# microzed_sd_v0_5_r1_1.net
KiCad netlist of a schematic drawn in EAGLE
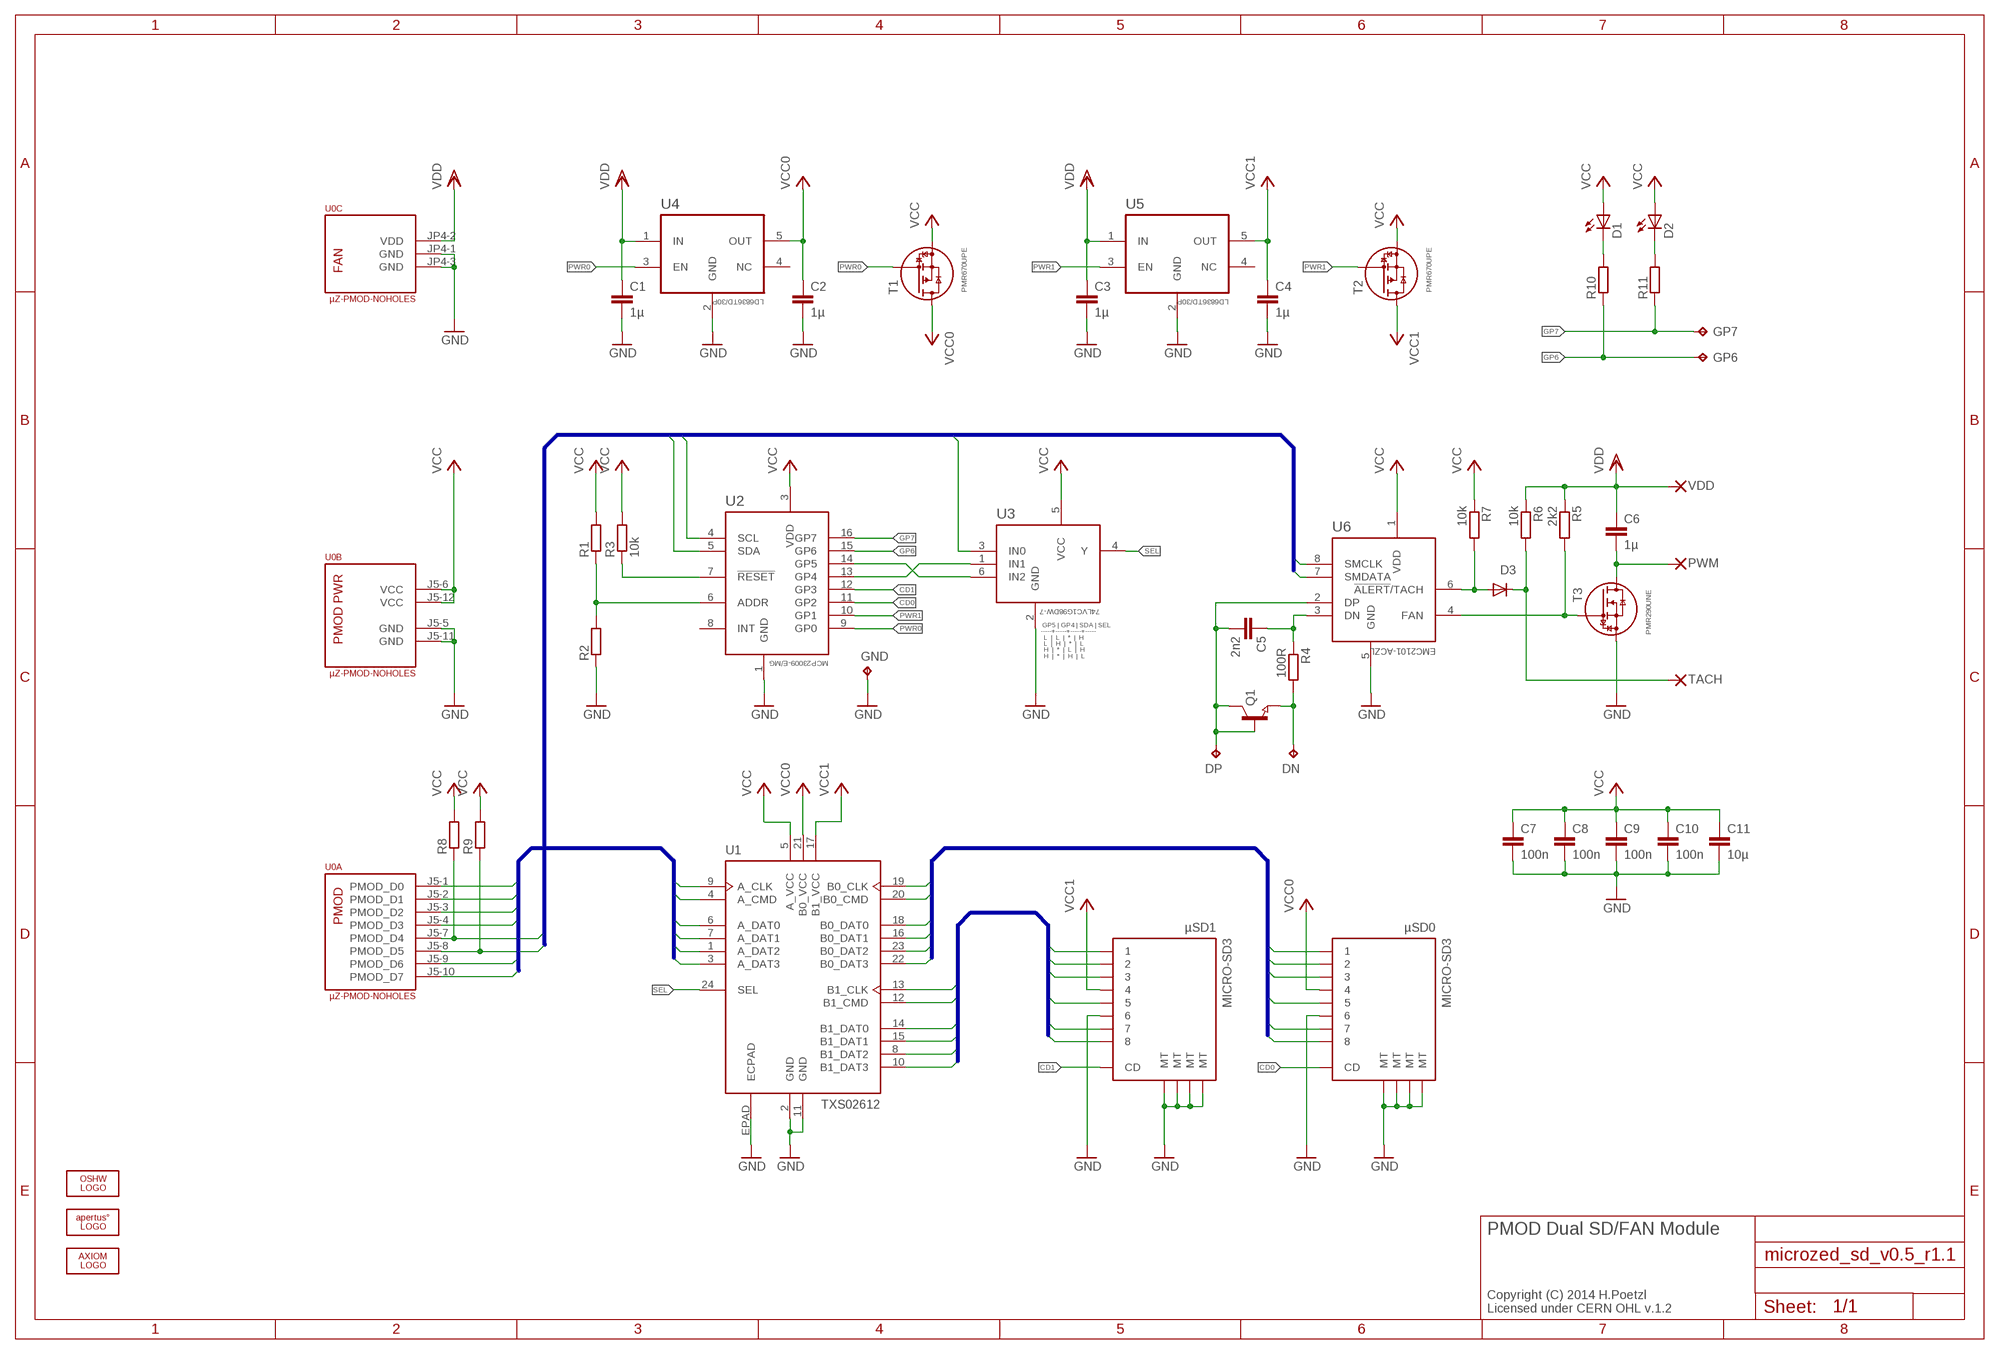
[diagram p0: schematic, sheet 1]

(export (version "E")
  (design (tool "Eeschema 10.0.6"))
  (components
    (comp (ref "C1")
      (value "1µ")
      (footprint "eagle-import:C0402K")
      (libsource (lib "eagle-import") (part "C-EUC0402K"))
    )
    (comp (ref "C2")
      (value "1µ")
      (footprint "eagle-import:C0402K")
      (libsource (lib "eagle-import") (part "C-EUC0402K"))
    )
    (comp (ref "C3")
      (value "1µ")
      (footprint "eagle-import:C0402K")
      (libsource (lib "eagle-import") (part "C-EUC0402K"))
    )
    (comp (ref "C4")
      (value "1µ")
      (footprint "eagle-import:C0402K")
      (libsource (lib "eagle-import") (part "C-EUC0402K"))
    )
    (comp (ref "C5")
      (value "2n2")
      (footprint "eagle-import:C0402K")
      (libsource (lib "eagle-import") (part "C-EUC0402K"))
    )
    (comp (ref "C6")
      (value "1µ")
      (footprint "eagle-import:C0402K")
      (libsource (lib "eagle-import") (part "C-EUC0402K"))
    )
    (comp (ref "C7")
      (value "100n")
      (footprint "eagle-import:C0402K")
      (libsource (lib "eagle-import") (part "C-EUC0402K"))
    )
    (comp (ref "C8")
      (value "100n")
      (footprint "eagle-import:C0402K")
      (libsource (lib "eagle-import") (part "C-EUC0402K"))
    )
    (comp (ref "C9")
      (value "100n")
      (footprint "eagle-import:C0402K")
      (libsource (lib "eagle-import") (part "C-EUC0402K"))
    )
    (comp (ref "C10")
      (value "100n")
      (footprint "eagle-import:C0402K")
      (libsource (lib "eagle-import") (part "C-EUC0402K"))
    )
    (comp (ref "C11")
      (value "10µ")
      (footprint "eagle-import:C0603K")
      (libsource (lib "eagle-import") (part "C-EUC0603K"))
    )
    (comp (ref "D1")
      (value "LEDCHIPLED_0603")
      (footprint "eagle-import:CHIPLED_0603")
      (libsource (lib "eagle-import") (part "LEDCHIPLED_0603"))
    )
    (comp (ref "D2")
      (value "LEDCHIPLED_0603")
      (footprint "eagle-import:CHIPLED_0603")
      (libsource (lib "eagle-import") (part "LEDCHIPLED_0603"))
    )
    (comp (ref "D3")
      (value "DIODE-MICROMELF-W")
      (footprint "eagle-import:MICROMELF-W")
      (libsource (lib "eagle-import") (part "DIODE-MICROMELF-W"))
    )
    (comp (ref "DN")
      (value "TPTP20R")
      (footprint "eagle-import:TP20R")
      (libsource (lib "eagle-import") (part "TPTP20R"))
    )
    (comp (ref "DP")
      (value "TPTP20R")
      (footprint "eagle-import:TP20R")
      (libsource (lib "eagle-import") (part "TPTP20R"))
    )
    (comp (ref "GND")
      (value "TPTP20R")
      (footprint "eagle-import:TP20R")
      (libsource (lib "eagle-import") (part "TPTP20R"))
    )
    (comp (ref "GP6")
      (value "TPTP20R")
      (footprint "eagle-import:TP20R")
      (libsource (lib "eagle-import") (part "TPTP20R"))
    )
    (comp (ref "GP7")
      (value "TPTP20R")
      (footprint "eagle-import:TP20R")
      (libsource (lib "eagle-import") (part "TPTP20R"))
    )
    (comp (ref "LOGO1")
      (value "OSHW_LOGO_FILLX0100-NT")
      (footprint "eagle-import:OSHW_FILLX100_NOTEXT")
      (libsource (lib "eagle-import") (part "OSHW_LOGO_FILLX0100-NT"))
    )
    (comp (ref "PWM")
      (value "WIREPAD1,85/1,0_SQ")
      (footprint "eagle-import:1,85_1,0_SQ")
      (libsource (lib "eagle-import") (part "WIREPAD1,85/1,0_SQ"))
    )
    (comp (ref "Q1")
      (value "NPN-TRANSISTOR_SOT23")
      (footprint "eagle-import:SOT23")
      (libsource (lib "eagle-import") (part "NPN-TRANSISTOR_SOT23"))
    )
    (comp (ref "R1")
      (value "R-EU_R0402")
      (footprint "eagle-import:R0402")
      (libsource (lib "eagle-import") (part "R-EU_R0402"))
    )
    (comp (ref "R2")
      (value "R-EU_R0402")
      (footprint "eagle-import:R0402")
      (libsource (lib "eagle-import") (part "R-EU_R0402"))
    )
    (comp (ref "R3")
      (value "10k")
      (footprint "eagle-import:R0402")
      (libsource (lib "eagle-import") (part "R-EU_R0402"))
    )
    (comp (ref "R4")
      (value "100R")
      (footprint "eagle-import:R0402")
      (libsource (lib "eagle-import") (part "R-EU_R0402"))
    )
    (comp (ref "R5")
      (value "2k2")
      (footprint "eagle-import:R0402")
      (libsource (lib "eagle-import") (part "R-EU_R0402"))
    )
    (comp (ref "R6")
      (value "10k")
      (footprint "eagle-import:R0402")
      (libsource (lib "eagle-import") (part "R-EU_R0402"))
    )
    (comp (ref "R7")
      (value "10k")
      (footprint "eagle-import:R0402")
      (libsource (lib "eagle-import") (part "R-EU_R0402"))
    )
    (comp (ref "R8")
      (value "R-EU_R0402")
      (footprint "eagle-import:R0402")
      (libsource (lib "eagle-import") (part "R-EU_R0402"))
    )
    (comp (ref "R9")
      (value "R-EU_R0402")
      (footprint "eagle-import:R0402")
      (libsource (lib "eagle-import") (part "R-EU_R0402"))
    )
    (comp (ref "R10")
      (value "R-EU_R0402")
      (footprint "eagle-import:R0402")
      (libsource (lib "eagle-import") (part "R-EU_R0402"))
    )
    (comp (ref "R11")
      (value "R-EU_R0402")
      (footprint "eagle-import:R0402")
      (libsource (lib "eagle-import") (part "R-EU_R0402"))
    )
    (comp (ref "T1")
      (value "PMR670UPE")
      (footprint "eagle-import:SOT416")
      (libsource (lib "eagle-import") (part "PMR670UPE"))
    )
    (comp (ref "T2")
      (value "PMR670UPE")
      (footprint "eagle-import:SOT416")
      (libsource (lib "eagle-import") (part "PMR670UPE"))
    )
    (comp (ref "T3")
      (value "PMR290UNE")
      (footprint "eagle-import:SOT416")
      (libsource (lib "eagle-import") (part "PMR290UNE"))
    )
    (comp (ref "TACH")
      (value "WIREPAD1,85/1,0")
      (footprint "eagle-import:1,85_1,0")
      (libsource (lib "eagle-import") (part "WIREPAD1,85/1,0"))
    )
    (comp (ref "U$1")
      (value "APERTUS_LOGO334X100")
      (footprint "eagle-import:APERTUS_LOGO_334X100")
      (libsource (lib "eagle-import") (part "APERTUS_LOGO334X100"))
    )
    (comp (ref "U$13")
      (value "AXIOM_LOGO525X80")
      (footprint "eagle-import:AXIOM_LOGO_525X80")
      (libsource (lib "eagle-import") (part "AXIOM_LOGO525X80"))
    )
    (comp (ref "U0")
      (value "µZ-PMOD-NOHOLES")
      (footprint "eagle-import:µZ-TOP-NOHOLES")
      (libsource (lib "eagle-import") (part "µZ-PMOD-NOHOLES"))
    )
    (comp (ref "U1")
      (value "TXS02612")
      (footprint "eagle-import:S-PWQFN-N24")
      (libsource (lib "eagle-import") (part "TXS02612"))
    )
    (comp (ref "U2")
      (value "MCP23009-E/MG")
      (footprint "eagle-import:QFN50P300X300X80-17N")
      (libsource (lib "eagle-import") (part "MCP23009-E/MG"))
    )
    (comp (ref "U3")
      (value "74LVC1G98DW-7")
      (footprint "eagle-import:SOT65P210X110-6N")
      (libsource (lib "eagle-import") (part "74LVC1G98DW-7"))
    )
    (comp (ref "U4")
      (value "LD6836TD/30P")
      (footprint "eagle-import:SOT95P275X110-5N")
      (libsource (lib "eagle-import") (part "LD6836TD/30P"))
    )
    (comp (ref "U5")
      (value "LD6836TD/30P")
      (footprint "eagle-import:SOT95P275X110-5N")
      (libsource (lib "eagle-import") (part "LD6836TD/30P"))
    )
    (comp (ref "U6")
      (value "EMC2101-ACZL")
      (footprint "eagle-import:SOP65P490X110-8N")
      (fields (field (name "MPN") "EMC2101-ACZL-TR "))
      (libsource (lib "eagle-import") (part "EMC2101-ACZL"))
    )
    (comp (ref "VDD")
      (value "WIREPAD1,85/1,0")
      (footprint "eagle-import:1,85_1,0")
      (libsource (lib "eagle-import") (part "WIREPAD1,85/1,0"))
    )
    (comp (ref "µSD0")
      (value "MICRO-SD3")
      (footprint "eagle-import:TF-MICRO-SD_PP3")
      (libsource (lib "eagle-import") (part "MICRO-SD3"))
    )
    (comp (ref "µSD1")
      (value "MICRO-SD3")
      (footprint "eagle-import:TF-MICRO-SD_PP3")
      (libsource (lib "eagle-import") (part "MICRO-SD3"))
    )
  )
  (nets
    (net (code "1") (name "/A_CLK") (class "Default")
      (node (ref "U0") (pin "J5-4") (pinfunction "PMOD_D3_J5-4") (pintype "bidirectional"))
      (node (ref "U1") (pin "9") (pinfunction "A_CLK_9") (pintype "input"))
    )
    (net (code "2") (name "/A_CMD") (class "Default")
      (node (ref "U0") (pin "J5-3") (pinfunction "PMOD_D2_J5-3") (pintype "bidirectional"))
      (node (ref "U1") (pin "4") (pinfunction "A_CMD_4") (pintype "bidirectional"))
    )
    (net (code "3") (name "/A_DAT0") (class "Default")
      (node (ref "U0") (pin "J5-2") (pinfunction "PMOD_D1_J5-2") (pintype "bidirectional"))
      (node (ref "U1") (pin "6") (pinfunction "A_DAT0_6") (pintype "bidirectional"))
    )
    (net (code "4") (name "/A_DAT1") (class "Default")
      (node (ref "U0") (pin "J5-1") (pinfunction "PMOD_D0_J5-1") (pintype "bidirectional"))
      (node (ref "U1") (pin "7") (pinfunction "A_DAT1_7") (pintype "bidirectional"))
    )
    (net (code "5") (name "/A_DAT2") (class "Default")
      (node (ref "U0") (pin "J5-9") (pinfunction "PMOD_D6_J5-9") (pintype "bidirectional"))
      (node (ref "U1") (pin "1") (pinfunction "A_DAT2_1") (pintype "bidirectional"))
    )
    (net (code "6") (name "/A_DAT3") (class "Default")
      (node (ref "U0") (pin "J5-10") (pinfunction "PMOD_D7_J5-10") (pintype "bidirectional"))
      (node (ref "U1") (pin "3") (pinfunction "A_DAT3_3") (pintype "bidirectional"))
    )
    (net (code "7") (name "/B0_CLK") (class "Default")
      (node (ref "U1") (pin "19") (pinfunction "B0_CLK_19") (pintype "output"))
      (node (ref "µSD0") (pin "5") (pinfunction "5_5") (pintype "bidirectional"))
    )
    (net (code "8") (name "/B0_CMD") (class "Default")
      (node (ref "U1") (pin "20") (pinfunction "B0_CMD_20") (pintype "bidirectional"))
      (node (ref "µSD0") (pin "3") (pinfunction "3_3") (pintype "bidirectional"))
    )
    (net (code "9") (name "/B0_DAT0") (class "Default")
      (node (ref "U1") (pin "18") (pinfunction "B0_DAT0_18") (pintype "bidirectional"))
      (node (ref "µSD0") (pin "7") (pinfunction "7_7") (pintype "bidirectional"))
    )
    (net (code "10") (name "/B0_DAT1") (class "Default")
      (node (ref "U1") (pin "16") (pinfunction "B0_DAT1_16") (pintype "bidirectional"))
      (node (ref "µSD0") (pin "8") (pinfunction "8_8") (pintype "bidirectional"))
    )
    (net (code "11") (name "/B0_DAT2") (class "Default")
      (node (ref "U1") (pin "23") (pinfunction "B0_DAT2_23") (pintype "bidirectional"))
      (node (ref "µSD0") (pin "1") (pinfunction "1_1") (pintype "bidirectional"))
    )
    (net (code "12") (name "/B0_DAT3") (class "Default")
      (node (ref "U1") (pin "22") (pinfunction "B0_DAT3_22") (pintype "bidirectional"))
      (node (ref "µSD0") (pin "2") (pinfunction "2_2") (pintype "bidirectional"))
    )
    (net (code "13") (name "/B1_CLK") (class "Default")
      (node (ref "U1") (pin "13") (pinfunction "B1_CLK_13") (pintype "output"))
      (node (ref "µSD1") (pin "5") (pinfunction "5_5") (pintype "bidirectional"))
    )
    (net (code "14") (name "/B1_CMD") (class "Default")
      (node (ref "U1") (pin "12") (pinfunction "B1_CMD_12") (pintype "bidirectional"))
      (node (ref "µSD1") (pin "3") (pinfunction "3_3") (pintype "bidirectional"))
    )
    (net (code "15") (name "/B1_DAT0") (class "Default")
      (node (ref "U1") (pin "14") (pinfunction "B1_DAT0_14") (pintype "bidirectional"))
      (node (ref "µSD1") (pin "7") (pinfunction "7_7") (pintype "bidirectional"))
    )
    (net (code "16") (name "/B1_DAT1") (class "Default")
      (node (ref "U1") (pin "15") (pinfunction "B1_DAT1_15") (pintype "bidirectional"))
      (node (ref "µSD1") (pin "8") (pinfunction "8_8") (pintype "bidirectional"))
    )
    (net (code "17") (name "/B1_DAT2") (class "Default")
      (node (ref "U1") (pin "8") (pinfunction "B1_DAT2_8") (pintype "bidirectional"))
      (node (ref "µSD1") (pin "1") (pinfunction "1_1") (pintype "bidirectional"))
    )
    (net (code "18") (name "/B1_DAT3") (class "Default")
      (node (ref "U1") (pin "10") (pinfunction "B1_DAT3_10") (pintype "bidirectional"))
      (node (ref "µSD1") (pin "2") (pinfunction "2_2") (pintype "bidirectional"))
    )
    (net (code "19") (name "/SCL") (class "Default")
      (node (ref "R8") (pin "1") (pinfunction "1_1") (pintype "passive"))
      (node (ref "U0") (pin "J5-7") (pinfunction "PMOD_D4_J5-7") (pintype "bidirectional"))
      (node (ref "U2") (pin "4") (pinfunction "SCL_4") (pintype "input"))
      (node (ref "U6") (pin "8") (pinfunction "SMCLK_8") (pintype "input"))
    )
    (net (code "20") (name "/SDA") (class "Default")
      (node (ref "R9") (pin "1") (pinfunction "1_1") (pintype "passive"))
      (node (ref "U0") (pin "J5-8") (pinfunction "PMOD_D5_J5-8") (pintype "bidirectional"))
      (node (ref "U2") (pin "5") (pinfunction "SDA_5") (pintype "bidirectional"))
      (node (ref "U3") (pin "3") (pinfunction "IN0_3") (pintype "input"))
      (node (ref "U6") (pin "7") (pinfunction "SMDATA_7") (pintype "bidirectional"))
    )
    (net (code "21") (name "CD0") (class "Default")
      (node (ref "U2") (pin "11") (pinfunction "GP2_11") (pintype "bidirectional"))
      (node (ref "µSD0") (pin "CD") (pinfunction "CD_CD") (pintype "bidirectional"))
    )
    (net (code "22") (name "CD1") (class "Default")
      (node (ref "U2") (pin "12") (pinfunction "GP3_12") (pintype "bidirectional"))
      (node (ref "µSD1") (pin "CD") (pinfunction "CD_CD") (pintype "bidirectional"))
    )
    (net (code "23") (name "GND") (class "Default")
      (node (ref "C1") (pin "2") (pinfunction "2_2") (pintype "passive"))
      (node (ref "C10") (pin "2") (pinfunction "2_2") (pintype "passive"))
      (node (ref "C11") (pin "2") (pinfunction "2_2") (pintype "passive"))
      (node (ref "C2") (pin "2") (pinfunction "2_2") (pintype "passive"))
      (node (ref "C3") (pin "2") (pinfunction "2_2") (pintype "passive"))
      (node (ref "C4") (pin "2") (pinfunction "2_2") (pintype "passive"))
      (node (ref "C7") (pin "2") (pinfunction "2_2") (pintype "passive"))
      (node (ref "C8") (pin "2") (pinfunction "2_2") (pintype "passive"))
      (node (ref "C9") (pin "2") (pinfunction "2_2") (pintype "passive"))
      (node (ref "GND") (pin "TP") (pinfunction "TP_TP") (pintype "input"))
      (node (ref "R2") (pin "1") (pinfunction "1_1") (pintype "passive"))
      (node (ref "T3") (pin "2") (pinfunction "S_2") (pintype "passive"))
      (node (ref "U0") (pin "J5-11") (pinfunction "GND_J5-11") (pintype "power_in"))
      (node (ref "U0") (pin "J5-5") (pinfunction "GND_J5-5") (pintype "power_in"))
      (node (ref "U0") (pin "JP4-1") (pinfunction "GND_JP4-1") (pintype "power_in"))
      (node (ref "U0") (pin "JP4-3") (pinfunction "GND_JP4-3") (pintype "power_in"))
      (node (ref "U1") (pin "11") (pinfunction "GND_11") (pintype "power_in"))
      (node (ref "U1") (pin "2") (pinfunction "GND_2") (pintype "power_in"))
      (node (ref "U1") (pin "EPAD") (pinfunction "ECPAD_EPAD") (pintype "power_in"))
      (node (ref "U2") (pin "1") (pinfunction "GND_1") (pintype "power_in"))
      (node (ref "U3") (pin "2") (pinfunction "GND_2") (pintype "passive"))
      (node (ref "U4") (pin "2") (pinfunction "GND_2") (pintype "passive"))
      (node (ref "U5") (pin "2") (pinfunction "GND_2") (pintype "passive"))
      (node (ref "U6") (pin "5") (pinfunction "GND_5") (pintype "power_in"))
      (node (ref "µSD0") (pin "6") (pinfunction "6_6") (pintype "bidirectional"))
      (node (ref "µSD0") (pin "MT1") (pinfunction "MT_MT1") (pintype "power_in"))
      (node (ref "µSD0") (pin "MT2") (pinfunction "MT_MT2") (pintype "power_in"))
      (node (ref "µSD0") (pin "MT3") (pinfunction "MT_MT3") (pintype "power_in"))
      (node (ref "µSD0") (pin "MT4") (pinfunction "MT_MT4") (pintype "power_in"))
      (node (ref "µSD1") (pin "6") (pinfunction "6_6") (pintype "bidirectional"))
      (node (ref "µSD1") (pin "MT1") (pinfunction "MT_MT1") (pintype "power_in"))
      (node (ref "µSD1") (pin "MT2") (pinfunction "MT_MT2") (pintype "power_in"))
      (node (ref "µSD1") (pin "MT3") (pinfunction "MT_MT3") (pintype "power_in"))
      (node (ref "µSD1") (pin "MT4") (pinfunction "MT_MT4") (pintype "power_in"))
    )
    (net (code "24") (name "GP6") (class "Default")
      (node (ref "GP6") (pin "TP") (pinfunction "TP_TP") (pintype "input"))
      (node (ref "R10") (pin "1") (pinfunction "1_1") (pintype "passive"))
      (node (ref "U2") (pin "15") (pinfunction "GP6_15") (pintype "bidirectional"))
    )
    (net (code "25") (name "GP7") (class "Default")
      (node (ref "GP7") (pin "TP") (pinfunction "TP_TP") (pintype "input"))
      (node (ref "R11") (pin "1") (pinfunction "1_1") (pintype "passive"))
      (node (ref "U2") (pin "16") (pinfunction "GP7_16") (pintype "bidirectional"))
    )
    (net (code "26") (name "Net-(D1-PadC)") (class "Default")
      (node (ref "D1") (pin "C") (pinfunction "C_C") (pintype "passive"))
      (node (ref "R10") (pin "2") (pinfunction "2_2") (pintype "passive"))
    )
    (net (code "27") (name "Net-(D2-PadC)") (class "Default")
      (node (ref "D2") (pin "C") (pinfunction "C_C") (pintype "passive"))
      (node (ref "R11") (pin "2") (pinfunction "2_2") (pintype "passive"))
    )
    (net (code "28") (name "Net-(PWM-P)") (class "Default")
      (node (ref "C6") (pin "2") (pinfunction "2_2") (pintype "passive"))
      (node (ref "PWM") (pin "1") (pinfunction "P_1") (pintype "passive"))
      (node (ref "T3") (pin "3") (pinfunction "D_3") (pintype "passive"))
    )
    (net (code "29") (name "Net-(Q1-B)") (class "Default")
      (node (ref "C5") (pin "2") (pinfunction "2_2") (pintype "passive"))
      (node (ref "DP") (pin "TP") (pinfunction "TP_TP") (pintype "input"))
      (node (ref "Q1") (pin "1") (pinfunction "B_1") (pintype "passive"))
      (node (ref "Q1") (pin "3") (pinfunction "C_3") (pintype "passive"))
      (node (ref "U6") (pin "2") (pinfunction "DP_2") (pintype "passive"))
    )
    (net (code "30") (name "Net-(Q1-E)") (class "Default")
      (node (ref "DN") (pin "TP") (pinfunction "TP_TP") (pintype "input"))
      (node (ref "Q1") (pin "2") (pinfunction "E_2") (pintype "passive"))
      (node (ref "R4") (pin "2") (pinfunction "2_2") (pintype "passive"))
    )
    (net (code "31") (name "Net-(T3-G)") (class "Default")
      (node (ref "R5") (pin "2") (pinfunction "2_2") (pintype "passive"))
      (node (ref "T3") (pin "1") (pinfunction "G_1") (pintype "passive"))
      (node (ref "U6") (pin "4") (pinfunction "FAN_4") (pintype "output"))
    )
    (net (code "32") (name "Net-(TACH-P)") (class "Default")
      (node (ref "D3") (pin "C") (pinfunction "C_C") (pintype "passive"))
      (node (ref "R6") (pin "2") (pinfunction "2_2") (pintype "passive"))
      (node (ref "TACH") (pin "1") (pinfunction "P_1") (pintype "passive"))
    )
    (net (code "33") (name "Net-(U2-ADDR)") (class "Default")
      (node (ref "R1") (pin "1") (pinfunction "1_1") (pintype "passive"))
      (node (ref "R2") (pin "2") (pinfunction "2_2") (pintype "passive"))
      (node (ref "U2") (pin "6") (pinfunction "ADDR_6") (pintype "input"))
    )
    (net (code "34") (name "Net-(U2-GP4)") (class "Default")
      (node (ref "U2") (pin "13") (pinfunction "GP4_13") (pintype "bidirectional"))
      (node (ref "U3") (pin "1") (pinfunction "IN1_1") (pintype "input"))
    )
    (net (code "35") (name "Net-(U2-GP5)") (class "Default")
      (node (ref "U2") (pin "14") (pinfunction "GP5_14") (pintype "bidirectional"))
      (node (ref "U3") (pin "6") (pinfunction "IN2_6") (pintype "input"))
    )
    (net (code "36") (name "Net-(U2-~{RESET})") (class "Default")
      (node (ref "R3") (pin "1") (pinfunction "1_1") (pintype "passive"))
      (node (ref "U2") (pin "7") (pinfunction "~{RESET}_7") (pintype "input"))
    )
    (net (code "37") (name "Net-(U6-DN)") (class "Default")
      (node (ref "C5") (pin "1") (pinfunction "1_1") (pintype "passive"))
      (node (ref "R4") (pin "1") (pinfunction "1_1") (pintype "passive"))
      (node (ref "U6") (pin "3") (pinfunction "DN_3") (pintype "passive"))
    )
    (net (code "38") (name "Net-(U6-~{ALERT}{slash}TACH)") (class "Default")
      (node (ref "D3") (pin "A") (pinfunction "A_A") (pintype "passive"))
      (node (ref "R7") (pin "2") (pinfunction "2_2") (pintype "passive"))
      (node (ref "U6") (pin "6") (pinfunction "~{ALERT}/TACH_6") (pintype "bidirectional"))
    )
    (net (code "39") (name "PWR0") (class "Default")
      (node (ref "T1") (pin "1") (pinfunction "G_1") (pintype "passive"))
      (node (ref "U2") (pin "9") (pinfunction "GP0_9") (pintype "bidirectional"))
      (node (ref "U4") (pin "3") (pinfunction "EN_3") (pintype "input"))
    )
    (net (code "40") (name "PWR1") (class "Default")
      (node (ref "T2") (pin "1") (pinfunction "G_1") (pintype "passive"))
      (node (ref "U2") (pin "10") (pinfunction "GP1_10") (pintype "bidirectional"))
      (node (ref "U5") (pin "3") (pinfunction "EN_3") (pintype "input"))
    )
    (net (code "41") (name "SEL") (class "Default")
      (node (ref "U1") (pin "24") (pinfunction "SEL_24") (pintype "input"))
      (node (ref "U3") (pin "4") (pinfunction "Y_4") (pintype "output"))
    )
    (net (code "42") (name "VCC") (class "Default")
      (node (ref "C10") (pin "1") (pinfunction "1_1") (pintype "passive"))
      (node (ref "C11") (pin "1") (pinfunction "1_1") (pintype "passive"))
      (node (ref "C7") (pin "1") (pinfunction "1_1") (pintype "passive"))
      (node (ref "C8") (pin "1") (pinfunction "1_1") (pintype "passive"))
      (node (ref "C9") (pin "1") (pinfunction "1_1") (pintype "passive"))
      (node (ref "D1") (pin "A") (pinfunction "A_A") (pintype "passive"))
      (node (ref "D2") (pin "A") (pinfunction "A_A") (pintype "passive"))
      (node (ref "R1") (pin "2") (pinfunction "2_2") (pintype "passive"))
      (node (ref "R3") (pin "2") (pinfunction "2_2") (pintype "passive"))
      (node (ref "R7") (pin "1") (pinfunction "1_1") (pintype "passive"))
      (node (ref "R8") (pin "2") (pinfunction "2_2") (pintype "passive"))
      (node (ref "R9") (pin "2") (pinfunction "2_2") (pintype "passive"))
      (node (ref "T1") (pin "2") (pinfunction "S_2") (pintype "passive"))
      (node (ref "T2") (pin "2") (pinfunction "S_2") (pintype "passive"))
      (node (ref "U0") (pin "J5-12") (pinfunction "VCC_J5-12") (pintype "power_in"))
      (node (ref "U0") (pin "J5-6") (pinfunction "VCC_J5-6") (pintype "power_in"))
      (node (ref "U1") (pin "5") (pinfunction "A_VCC_5") (pintype "power_in"))
      (node (ref "U2") (pin "3") (pinfunction "VDD_3") (pintype "power_in"))
      (node (ref "U3") (pin "5") (pinfunction "VCC_5") (pintype "power_in"))
      (node (ref "U6") (pin "1") (pinfunction "VDD_1") (pintype "power_in"))
    )
    (net (code "43") (name "VCC0") (class "Default")
      (node (ref "C2") (pin "1") (pinfunction "1_1") (pintype "passive"))
      (node (ref "T1") (pin "3") (pinfunction "D_3") (pintype "passive"))
      (node (ref "U1") (pin "21") (pinfunction "B0_VCC_21") (pintype "power_in"))
      (node (ref "U4") (pin "5") (pinfunction "OUT_5") (pintype "output"))
      (node (ref "µSD0") (pin "4") (pinfunction "4_4") (pintype "bidirectional"))
    )
    (net (code "44") (name "VCC1") (class "Default")
      (node (ref "C4") (pin "1") (pinfunction "1_1") (pintype "passive"))
      (node (ref "T2") (pin "3") (pinfunction "D_3") (pintype "passive"))
      (node (ref "U1") (pin "17") (pinfunction "B1_VCC_17") (pintype "power_in"))
      (node (ref "U5") (pin "5") (pinfunction "OUT_5") (pintype "output"))
      (node (ref "µSD1") (pin "4") (pinfunction "4_4") (pintype "bidirectional"))
    )
    (net (code "45") (name "VDD") (class "Default")
      (node (ref "C1") (pin "1") (pinfunction "1_1") (pintype "passive"))
      (node (ref "C3") (pin "1") (pinfunction "1_1") (pintype "passive"))
      (node (ref "C6") (pin "1") (pinfunction "1_1") (pintype "passive"))
      (node (ref "R5") (pin "1") (pinfunction "1_1") (pintype "passive"))
      (node (ref "R6") (pin "1") (pinfunction "1_1") (pintype "passive"))
      (node (ref "U0") (pin "JP4-2") (pinfunction "VDD_JP4-2") (pintype "power_in"))
      (node (ref "U4") (pin "1") (pinfunction "IN_1") (pintype "input"))
      (node (ref "U5") (pin "1") (pinfunction "IN_1") (pintype "input"))
      (node (ref "VDD") (pin "1") (pinfunction "P_1") (pintype "passive"))
    )
    (net (code "46") (name "unconnected-(U2-INT-Pad8)") (class "Default")
      (node (ref "U2") (pin "8") (pinfunction "INT_8") (pintype "output"))
    )
    (net (code "47") (name "unconnected-(U4-NC-Pad4)") (class "Default")
      (node (ref "U4") (pin "4") (pinfunction "NC_4") (pintype "no_connect"))
    )
    (net (code "48") (name "unconnected-(U5-NC-Pad4)") (class "Default")
      (node (ref "U5") (pin "4") (pinfunction "NC_4") (pintype "no_connect"))
    )
  )
)
